# Driver_PT5619_Table_SchDoc.net
KiCad netlist of a schematic drawn in Altium Designer
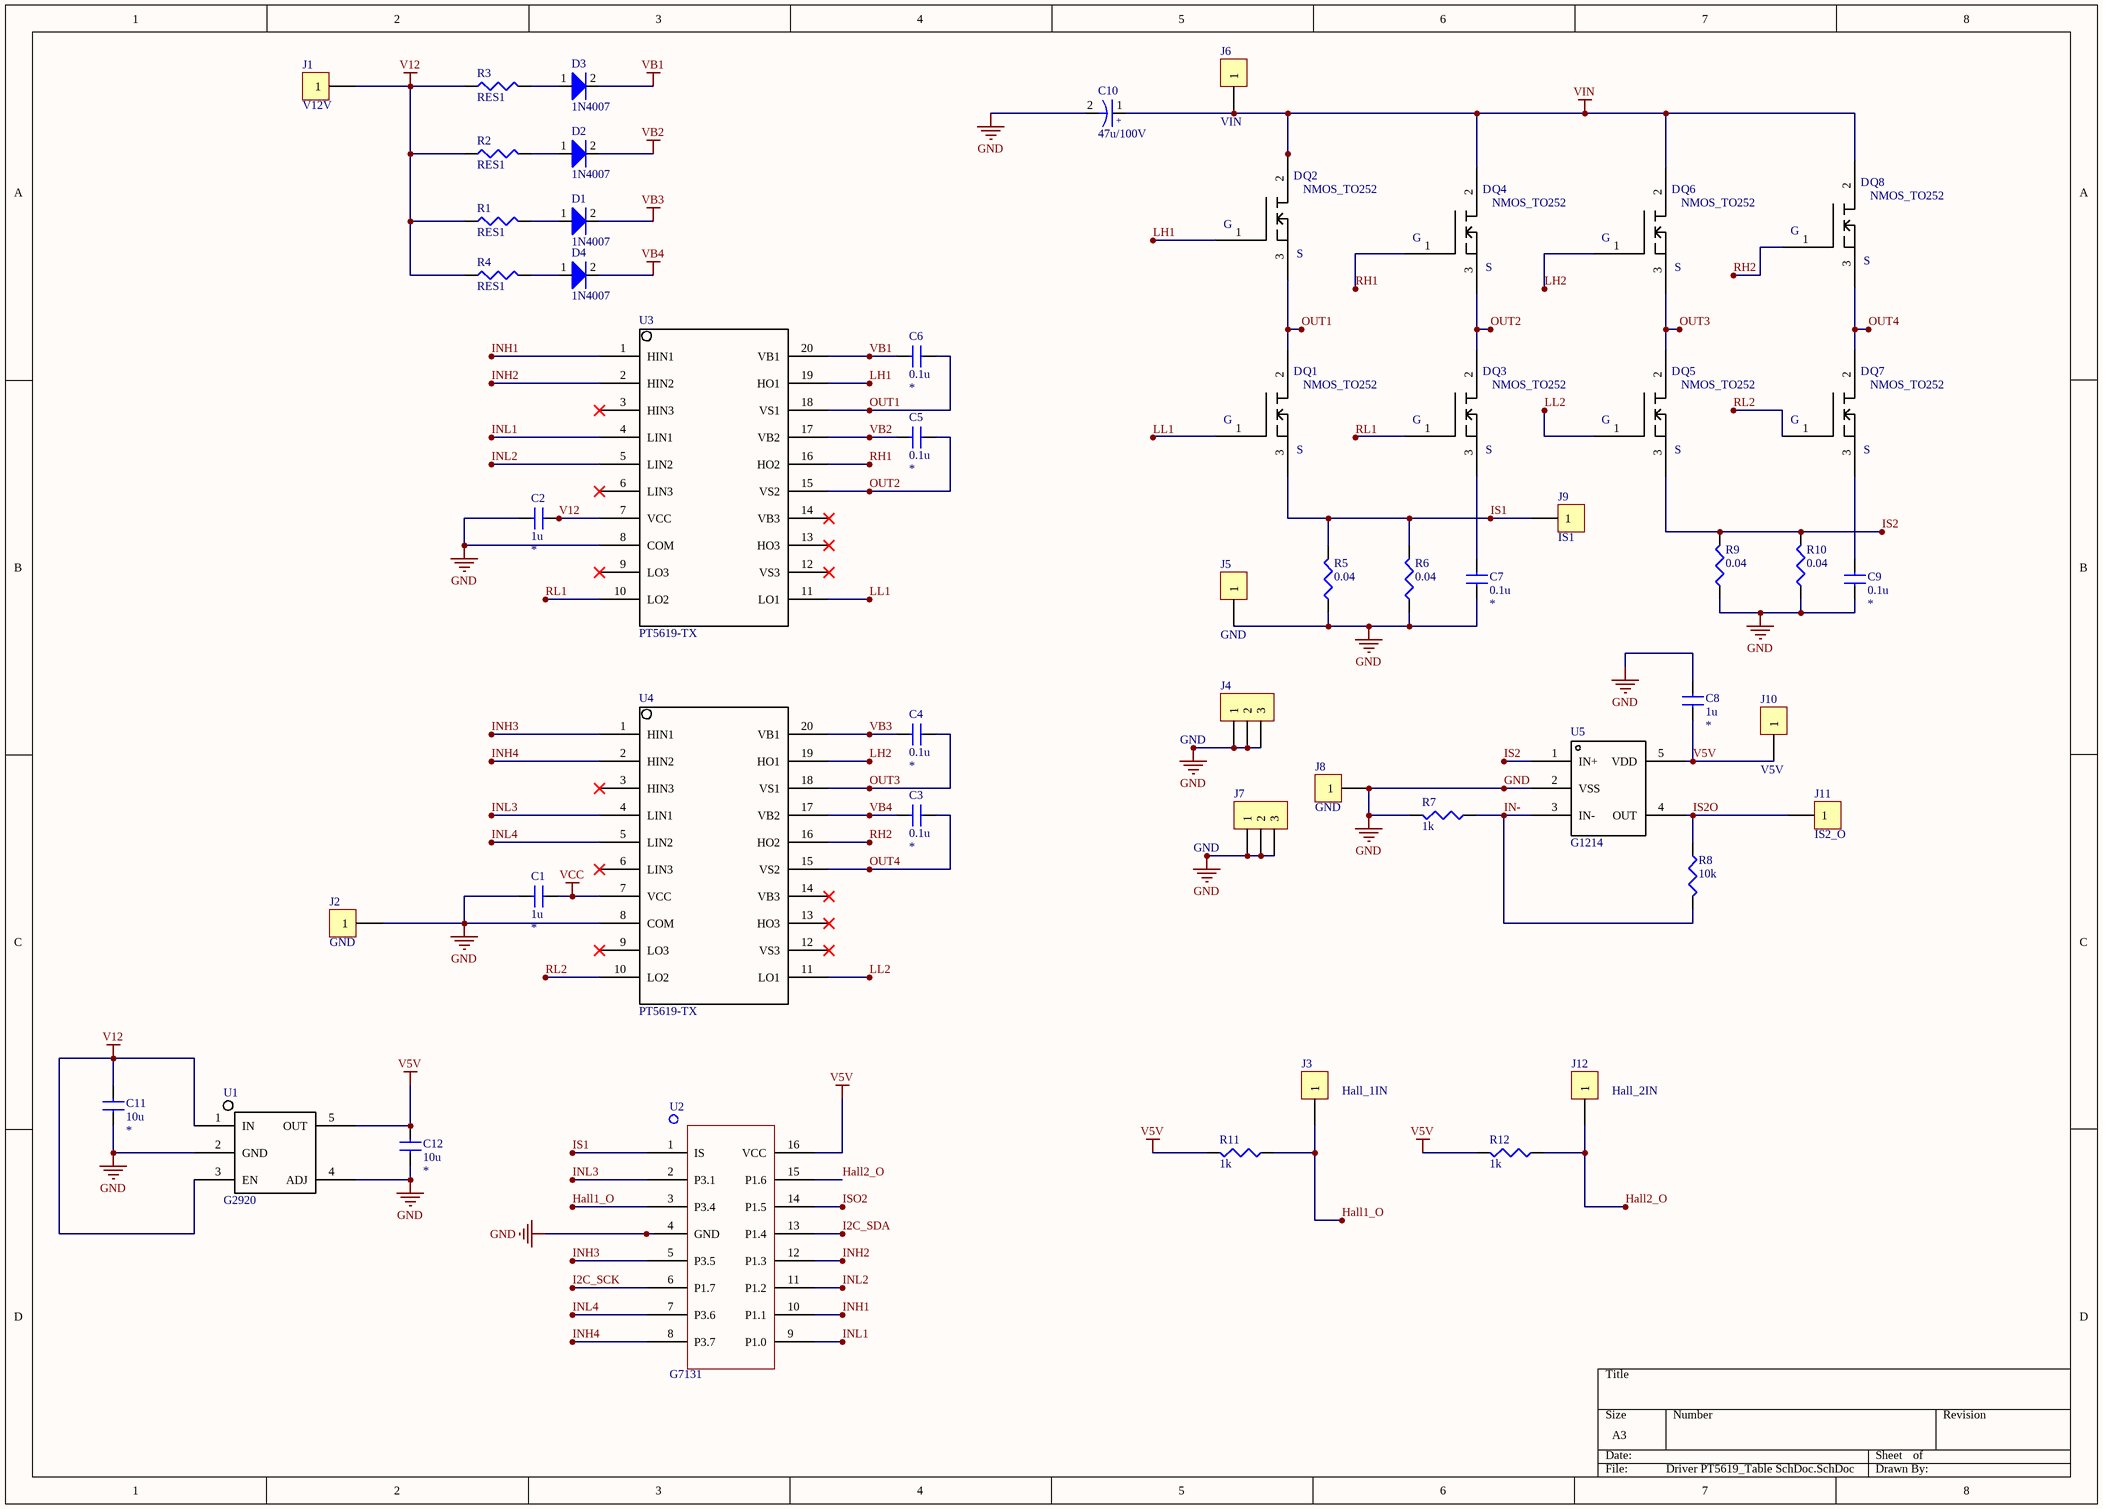
[diagram p0: Driver PT5619_Table SchDoc.SchDoc]

(export (version "E")
  (design (tool "Eeschema 10.0.6"))
  (components
    (comp (ref "C1")
      (value "1u")
      (footprint "0805_C")
      (description "Capacitor")
      (fields (field (name "IC") "*"))
      (libsource (lib "Neil-090810") (part "CAP"))
    )
    (comp (ref "C2")
      (value "1u")
      (footprint "0805_C")
      (description "Capacitor")
      (fields (field (name "IC") "*"))
      (libsource (lib "Neil-090810") (part "CAP"))
    )
    (comp (ref "C3")
      (value "0.1u")
      (footprint "0805_C")
      (description "Capacitor")
      (fields (field (name "IC") "*"))
      (libsource (lib "Neil-090810") (part "CAP"))
    )
    (comp (ref "C4")
      (value "0.1u")
      (footprint "0805_C")
      (description "Capacitor")
      (fields (field (name "IC") "*"))
      (libsource (lib "Neil-090810") (part "CAP"))
    )
    (comp (ref "C5")
      (value "0.1u")
      (footprint "0805_C")
      (description "Capacitor")
      (fields (field (name "IC") "*"))
      (libsource (lib "Neil-090810") (part "CAP"))
    )
    (comp (ref "C6")
      (value "0.1u")
      (footprint "0805_C")
      (description "Capacitor")
      (fields (field (name "IC") "*"))
      (libsource (lib "Neil-090810") (part "CAP"))
    )
    (comp (ref "C7")
      (value "0.1u")
      (footprint "0805_C")
      (description "Capacitor")
      (fields (field (name "IC") "*"))
      (libsource (lib "Neil-090810") (part "CAP"))
    )
    (comp (ref "C8")
      (value "1u")
      (footprint "0805_R")
      (description "Capacitor")
      (fields (field (name "IC") "*"))
      (libsource (lib "Neil-090810") (part "CAP"))
    )
    (comp (ref "C9")
      (value "0.1u")
      (footprint "0805_C")
      (description "Capacitor")
      (fields (field (name "IC") "*"))
      (libsource (lib "Neil-090810") (part "CAP"))
    )
    (comp (ref "C10")
      (value "47u/100V")
      (description "Capacitor")
      (libsource (lib "Neil-090810") (part "CAPACITOR POL"))
    )
    (comp (ref "C11")
      (value "10u")
      (description "Capacitor")
      (fields (field (name "IC") "*"))
      (libsource (lib "Neil-090810") (part "CAP"))
    )
    (comp (ref "C12")
      (value "10u")
      (description "Capacitor")
      (fields (field (name "IC") "*"))
      (libsource (lib "Neil-090810") (part "CAP"))
    )
    (comp (ref "D1")
      (value "1N4007")
      (footprint "DIODE-1206")
      (description "Junction Diode")
      (libsource (lib "Neil-090810") (part "DIODE_D"))
    )
    (comp (ref "D2")
      (value "1N4007")
      (footprint "DIODE-1206")
      (description "Junction Diode")
      (libsource (lib "Neil-090810") (part "DIODE_D"))
    )
    (comp (ref "D3")
      (value "1N4007")
      (footprint "DIODE-1206")
      (description "Junction Diode")
      (libsource (lib "Neil-090810") (part "DIODE_D"))
    )
    (comp (ref "D4")
      (value "1N4007")
      (footprint "DIODE-1206")
      (description "Junction Diode")
      (libsource (lib "Neil-090810") (part "DIODE_D"))
    )
    (comp (ref "J1")
      (value "V12V")
      (footprint "CON1")
      (description "Connector")
      (libsource (lib "") (part "CON1_2"))
    )
    (comp (ref "J2")
      (value "GND")
      (footprint "CON1")
      (description "Connector")
      (libsource (lib "") (part "CON1_2"))
    )
    (comp (ref "J3")
      (value "Hall_1IN")
      (description "Connector")
      (libsource (lib "Neil-090810") (part "CON1"))
    )
    (comp (ref "J4")
      (value "GND")
      (footprint "CON3")
      (description "Connector")
      (libsource (lib "Neil-090810") (part "CON3"))
    )
    (comp (ref "J5")
      (value "GND")
      (footprint "CON1")
      (description "Connector")
      (libsource (lib "Neil-090810") (part "CON1"))
    )
    (comp (ref "J6")
      (value "VIN")
      (footprint "CON1")
      (description "Connector")
      (libsource (lib "Neil-090810") (part "CON1"))
    )
    (comp (ref "J7")
      (value "GND")
      (footprint "CON3")
      (description "Connector")
      (libsource (lib "Neil-090810") (part "CON3"))
    )
    (comp (ref "J8")
      (value "GND")
      (footprint "CON1")
      (description "Connector")
      (libsource (lib "") (part "CON1_2"))
    )
    (comp (ref "J9")
      (value "IS1")
      (footprint "CON1s")
      (description "Connector")
      (libsource (lib "") (part "CON1_1"))
    )
    (comp (ref "J10")
      (value "V5V")
      (footprint "CON1")
      (description "Connector")
      (libsource (lib "Neil-090810") (part "CON1"))
    )
    (comp (ref "J11")
      (value "IS2_O")
      (footprint "CON1s")
      (description "Connector")
      (libsource (lib "") (part "CON1_1"))
    )
    (comp (ref "J12")
      (value "Hall_2IN")
      (description "Connector")
      (libsource (lib "Neil-090810") (part "CON1"))
    )
    (comp (ref "Q1")
      (value "NMOS_TO252")
      (footprint "TO220")
      (libsource (lib "Neil-090810") (part "NMOS_TO252"))
    )
    (comp (ref "Q2")
      (value "NMOS_TO252")
      (footprint "TO220")
      (libsource (lib "Neil-090810") (part "NMOS_TO252"))
    )
    (comp (ref "Q3")
      (value "NMOS_TO252")
      (footprint "TO220")
      (libsource (lib "Neil-090810") (part "NMOS_TO252"))
    )
    (comp (ref "Q4")
      (value "NMOS_TO252")
      (footprint "TO220")
      (libsource (lib "Neil-090810") (part "NMOS_TO252"))
    )
    (comp (ref "Q5")
      (value "NMOS_TO252")
      (footprint "TO220 - duplicate")
      (libsource (lib "Neil-090810") (part "NMOS_TO252"))
    )
    (comp (ref "Q6")
      (value "NMOS_TO252")
      (footprint "TO220")
      (libsource (lib "Neil-090810") (part "NMOS_TO252"))
    )
    (comp (ref "Q7")
      (value "NMOS_TO252")
      (footprint "TO220")
      (libsource (lib "Neil-090810") (part "NMOS_TO252"))
    )
    (comp (ref "Q8")
      (value "NMOS_TO252")
      (footprint "TO220")
      (libsource (lib "Neil-090810") (part "NMOS_TO252"))
    )
    (comp (ref "R1") (value "RES1") (footprint "0805_R") (libsource (lib "Neil-090810") (part "RES1")))
    (comp (ref "R2") (value "RES1") (footprint "0805_R") (libsource (lib "Neil-090810") (part "RES1")))
    (comp (ref "R3") (value "RES1") (footprint "0805_R") (libsource (lib "Neil-090810") (part "RES1")))
    (comp (ref "R4") (value "RES1") (footprint "0805_R") (libsource (lib "Neil-090810") (part "RES1")))
    (comp (ref "R5") (value "0.04") (footprint "2512") (libsource (lib "Neil-090810") (part "RES1")))
    (comp (ref "R6") (value "0.04") (footprint "2512") (libsource (lib "Neil-090810") (part "RES1")))
    (comp (ref "R7") (value "1k") (footprint "0805_R") (libsource (lib "Neil-090810") (part "RES1")))
    (comp (ref "R8") (value "10k") (footprint "0805_R") (libsource (lib "Neil-090810") (part "RES1")))
    (comp (ref "R9") (value "0.04") (footprint "2512") (libsource (lib "Neil-090810") (part "RES1")))
    (comp (ref "R10") (value "0.04") (footprint "2512") (libsource (lib "Neil-090810") (part "RES1")))
    (comp (ref "R11") (value "1k") (libsource (lib "Neil-090810") (part "RES1")))
    (comp (ref "R12") (value "1k") (libsource (lib "Neil-090810") (part "RES1")))
    (comp (ref "U1") (value "G2920") (libsource (lib "Neil-090810") (part "G2920")))
    (comp (ref "U2") (value "G7131") (libsource (lib "Neil-090810") (part "G7131")))
    (comp (ref "U3")
      (value "PT5619-TX")
      (footprint "TSSOP20")
      (libsource (lib "Neil-090810") (part "PT5619-TX"))
    )
    (comp (ref "U4")
      (value "PT5619-TX")
      (footprint "TSSOP20")
      (libsource (lib "Neil-090810") (part "PT5619-TX"))
    )
    (comp (ref "U5")
      (value "G1214")
      (footprint "SOT-23-5-G1211")
      (libsource (lib "Neil-090810") (part "G1214"))
    )
  )
  (nets
    (net (code "1") (name "/Hall1_O") (class "Default")
      (node (ref "J3") (pin "1") (pinfunction "1_1") (pintype "passive"))
      (node (ref "R11") (pin "1") (pinfunction "1_1") (pintype "passive"))
      (node (ref "U2") (pin "3") (pinfunction "P3.4_3") (pintype "passive"))
    )
    (net (code "2") (name "/Hall2_O") (class "Default")
      (node (ref "J12") (pin "1") (pinfunction "1_1") (pintype "passive"))
      (node (ref "R12") (pin "1") (pinfunction "1_1") (pintype "passive"))
      (node (ref "U2") (pin "15") (pinfunction "P1.6_15") (pintype "passive"))
    )
    (net (code "3") (name "/I2C_SCK") (class "Default")
      (node (ref "U2") (pin "6") (pinfunction "P1.7_6") (pintype "passive"))
    )
    (net (code "4") (name "/I2C_SDA") (class "Default")
      (node (ref "U2") (pin "13") (pinfunction "P1.4_13") (pintype "passive"))
    )
    (net (code "5") (name "/IN-") (class "Default")
      (node (ref "R7") (pin "1") (pinfunction "1_1") (pintype "passive"))
      (node (ref "R8") (pin "2") (pinfunction "2_2") (pintype "passive"))
      (node (ref "U5") (pin "3") (pinfunction "IN-_3") (pintype "passive"))
    )
    (net (code "6") (name "/INH1") (class "Default")
      (node (ref "U2") (pin "10") (pinfunction "P1.1_10") (pintype "passive"))
      (node (ref "U3") (pin "1") (pinfunction "HIN1_1") (pintype "passive"))
    )
    (net (code "7") (name "/INH2") (class "Default")
      (node (ref "U2") (pin "12") (pinfunction "P1.3_12") (pintype "passive"))
      (node (ref "U3") (pin "2") (pinfunction "HIN2_2") (pintype "passive"))
    )
    (net (code "8") (name "/INH3") (class "Default")
      (node (ref "U2") (pin "5") (pinfunction "P3.5_5") (pintype "passive"))
      (node (ref "U4") (pin "1") (pinfunction "HIN1_1") (pintype "passive"))
    )
    (net (code "9") (name "/INH4") (class "Default")
      (node (ref "U2") (pin "8") (pinfunction "P3.7_8") (pintype "passive"))
      (node (ref "U4") (pin "2") (pinfunction "HIN2_2") (pintype "passive"))
    )
    (net (code "10") (name "/INL1") (class "Default")
      (node (ref "U2") (pin "9") (pinfunction "P1.0_9") (pintype "passive"))
      (node (ref "U3") (pin "4") (pinfunction "LIN1_4") (pintype "passive"))
    )
    (net (code "11") (name "/INL2") (class "Default")
      (node (ref "U2") (pin "11") (pinfunction "P1.2_11") (pintype "passive"))
      (node (ref "U3") (pin "5") (pinfunction "LIN2_5") (pintype "passive"))
    )
    (net (code "12") (name "/INL3") (class "Default")
      (node (ref "U2") (pin "2") (pinfunction "P3.1_2") (pintype "passive"))
      (node (ref "U4") (pin "4") (pinfunction "LIN1_4") (pintype "passive"))
    )
    (net (code "13") (name "/INL4") (class "Default")
      (node (ref "U2") (pin "7") (pinfunction "P3.6_7") (pintype "passive"))
      (node (ref "U4") (pin "5") (pinfunction "LIN2_5") (pintype "passive"))
    )
    (net (code "14") (name "/IS1") (class "Default")
      (node (ref "J9") (pin "1") (pinfunction "1_1") (pintype "passive"))
      (node (ref "Q1") (pin "3") (pinfunction "S_3") (pintype "passive"))
      (node (ref "R5") (pin "2") (pinfunction "2_2") (pintype "passive"))
      (node (ref "R6") (pin "2") (pinfunction "2_2") (pintype "passive"))
      (node (ref "U2") (pin "1") (pinfunction "IS_1") (pintype "passive"))
    )
    (net (code "15") (name "/IS2") (class "Default")
      (node (ref "Q5") (pin "3") (pinfunction "S_3") (pintype "passive"))
      (node (ref "R10") (pin "2") (pinfunction "2_2") (pintype "passive"))
      (node (ref "R9") (pin "2") (pinfunction "2_2") (pintype "passive"))
      (node (ref "U5") (pin "1") (pinfunction "IN+_1") (pintype "passive"))
    )
    (net (code "16") (name "/IS2O") (class "Default")
      (node (ref "J11") (pin "1") (pinfunction "1_1") (pintype "passive"))
      (node (ref "R8") (pin "1") (pinfunction "1_1") (pintype "passive"))
      (node (ref "U5") (pin "4") (pinfunction "OUT_4") (pintype "passive"))
    )
    (net (code "17") (name "/ISO2") (class "Default")
      (node (ref "U2") (pin "14") (pinfunction "P1.5_14") (pintype "passive"))
    )
    (net (code "18") (name "/LH1") (class "Default")
      (node (ref "Q2") (pin "1") (pinfunction "G_1") (pintype "passive"))
      (node (ref "U3") (pin "19") (pinfunction "HO1_19") (pintype "passive"))
    )
    (net (code "19") (name "/LH2") (class "Default")
      (node (ref "Q6") (pin "1") (pinfunction "G_1") (pintype "passive"))
      (node (ref "U4") (pin "19") (pinfunction "HO1_19") (pintype "passive"))
    )
    (net (code "20") (name "/LL1") (class "Default")
      (node (ref "Q1") (pin "1") (pinfunction "G_1") (pintype "passive"))
      (node (ref "U3") (pin "11") (pinfunction "LO1_11") (pintype "passive"))
    )
    (net (code "21") (name "/LL2") (class "Default")
      (node (ref "Q5") (pin "1") (pinfunction "G_1") (pintype "passive"))
      (node (ref "U4") (pin "11") (pinfunction "LO1_11") (pintype "passive"))
    )
    (net (code "22") (name "/OUT1") (class "Default")
      (node (ref "C6") (pin "2") (pinfunction "2_2") (pintype "passive"))
      (node (ref "Q1") (pin "2") (pinfunction "D_2") (pintype "passive"))
      (node (ref "Q2") (pin "3") (pinfunction "S_3") (pintype "passive"))
      (node (ref "U3") (pin "18") (pinfunction "VS1_18") (pintype "passive"))
    )
    (net (code "23") (name "/OUT2") (class "Default")
      (node (ref "C5") (pin "2") (pinfunction "2_2") (pintype "passive"))
      (node (ref "Q3") (pin "2") (pinfunction "D_2") (pintype "passive"))
      (node (ref "Q4") (pin "3") (pinfunction "S_3") (pintype "passive"))
      (node (ref "U3") (pin "15") (pinfunction "VS2_15") (pintype "passive"))
    )
    (net (code "24") (name "/OUT3") (class "Default")
      (node (ref "C4") (pin "2") (pinfunction "2_2") (pintype "passive"))
      (node (ref "Q5") (pin "2") (pinfunction "D_2") (pintype "passive"))
      (node (ref "Q6") (pin "3") (pinfunction "S_3") (pintype "passive"))
      (node (ref "U4") (pin "18") (pinfunction "VS1_18") (pintype "passive"))
    )
    (net (code "25") (name "/OUT4") (class "Default")
      (node (ref "C3") (pin "2") (pinfunction "2_2") (pintype "passive"))
      (node (ref "Q7") (pin "2") (pinfunction "D_2") (pintype "passive"))
      (node (ref "Q8") (pin "3") (pinfunction "S_3") (pintype "passive"))
      (node (ref "U4") (pin "15") (pinfunction "VS2_15") (pintype "passive"))
    )
    (net (code "26") (name "/RH1") (class "Default")
      (node (ref "Q4") (pin "1") (pinfunction "G_1") (pintype "passive"))
      (node (ref "U3") (pin "16") (pinfunction "HO2_16") (pintype "passive"))
    )
    (net (code "27") (name "/RH2") (class "Default")
      (node (ref "Q8") (pin "1") (pinfunction "G_1") (pintype "passive"))
      (node (ref "U4") (pin "16") (pinfunction "HO2_16") (pintype "passive"))
    )
    (net (code "28") (name "/RL1") (class "Default")
      (node (ref "Q3") (pin "1") (pinfunction "G_1") (pintype "passive"))
      (node (ref "U3") (pin "10") (pinfunction "LO2_10") (pintype "passive"))
    )
    (net (code "29") (name "/RL2") (class "Default")
      (node (ref "Q7") (pin "1") (pinfunction "G_1") (pintype "passive"))
      (node (ref "U4") (pin "10") (pinfunction "LO2_10") (pintype "passive"))
    )
    (net (code "30") (name "GND") (class "Default")
      (node (ref "C1") (pin "2") (pinfunction "2_2") (pintype "passive"))
      (node (ref "C10") (pin "2") (pinfunction "2_2") (pintype "passive"))
      (node (ref "C11") (pin "2") (pinfunction "2_2") (pintype "passive"))
      (node (ref "C12") (pin "2") (pinfunction "2_2") (pintype "passive"))
      (node (ref "C2") (pin "1") (pinfunction "1_1") (pintype "passive"))
      (node (ref "C7") (pin "2") (pinfunction "2_2") (pintype "passive"))
      (node (ref "C8") (pin "2") (pinfunction "2_2") (pintype "passive"))
      (node (ref "C9") (pin "2") (pinfunction "2_2") (pintype "passive"))
      (node (ref "J2") (pin "1") (pinfunction "1_1") (pintype "passive"))
      (node (ref "J4") (pin "1") (pinfunction "1_1") (pintype "passive"))
      (node (ref "J4") (pin "2") (pinfunction "2_2") (pintype "passive"))
      (node (ref "J4") (pin "3") (pinfunction "3_3") (pintype "passive"))
      (node (ref "J5") (pin "1") (pinfunction "1_1") (pintype "passive"))
      (node (ref "J7") (pin "1") (pinfunction "1_1") (pintype "passive"))
      (node (ref "J7") (pin "2") (pinfunction "2_2") (pintype "passive"))
      (node (ref "J7") (pin "3") (pinfunction "3_3") (pintype "passive"))
      (node (ref "J8") (pin "1") (pinfunction "1_1") (pintype "passive"))
      (node (ref "R10") (pin "1") (pinfunction "1_1") (pintype "passive"))
      (node (ref "R5") (pin "1") (pinfunction "1_1") (pintype "passive"))
      (node (ref "R6") (pin "1") (pinfunction "1_1") (pintype "passive"))
      (node (ref "R7") (pin "2") (pinfunction "2_2") (pintype "passive"))
      (node (ref "R9") (pin "1") (pinfunction "1_1") (pintype "passive"))
      (node (ref "U1") (pin "2") (pinfunction "GND_2") (pintype "passive"))
      (node (ref "U1") (pin "4") (pinfunction "ADJ_4") (pintype "passive"))
      (node (ref "U2") (pin "4") (pinfunction "GND_4") (pintype "passive"))
      (node (ref "U3") (pin "8") (pinfunction "COM_8") (pintype "passive"))
      (node (ref "U4") (pin "8") (pinfunction "COM_8") (pintype "passive"))
      (node (ref "U5") (pin "2") (pinfunction "VSS_2") (pintype "passive"))
    )
    (net (code "31") (name "Net-(D1-n1)") (class "Default")
      (node (ref "D1") (pin "1") (pinfunction "n1_1") (pintype "passive"))
      (node (ref "R1") (pin "2") (pinfunction "2_2") (pintype "passive"))
    )
    (net (code "32") (name "Net-(D2-n1)") (class "Default")
      (node (ref "D2") (pin "1") (pinfunction "n1_1") (pintype "passive"))
      (node (ref "R2") (pin "2") (pinfunction "2_2") (pintype "passive"))
    )
    (net (code "33") (name "Net-(D3-n1)") (class "Default")
      (node (ref "D3") (pin "1") (pinfunction "n1_1") (pintype "passive"))
      (node (ref "R3") (pin "2") (pinfunction "2_2") (pintype "passive"))
    )
    (net (code "34") (name "Net-(D4-n1)") (class "Default")
      (node (ref "D4") (pin "1") (pinfunction "n1_1") (pintype "passive"))
      (node (ref "R4") (pin "2") (pinfunction "2_2") (pintype "passive"))
    )
    (net (code "35") (name "Net-(Q3-S)") (class "Default")
      (node (ref "C7") (pin "1") (pinfunction "1_1") (pintype "passive"))
      (node (ref "Q3") (pin "3") (pinfunction "S_3") (pintype "passive"))
    )
    (net (code "36") (name "Net-(Q7-S)") (class "Default")
      (node (ref "C9") (pin "1") (pinfunction "1_1") (pintype "passive"))
      (node (ref "Q7") (pin "3") (pinfunction "S_3") (pintype "passive"))
    )
    (net (code "37") (name "V5V") (class "Default")
      (node (ref "C12") (pin "1") (pinfunction "1_1") (pintype "passive"))
      (node (ref "C8") (pin "1") (pinfunction "1_1") (pintype "passive"))
      (node (ref "J10") (pin "1") (pinfunction "1_1") (pintype "passive"))
      (node (ref "R11") (pin "2") (pinfunction "2_2") (pintype "passive"))
      (node (ref "R12") (pin "2") (pinfunction "2_2") (pintype "passive"))
      (node (ref "U1") (pin "5") (pinfunction "OUT_5") (pintype "passive"))
      (node (ref "U2") (pin "16") (pinfunction "VCC_16") (pintype "passive"))
      (node (ref "U5") (pin "5") (pinfunction "VDD_5") (pintype "passive"))
    )
    (net (code "38") (name "V12") (class "Default")
      (node (ref "C11") (pin "1") (pinfunction "1_1") (pintype "passive"))
      (node (ref "C2") (pin "2") (pinfunction "2_2") (pintype "passive"))
      (node (ref "J1") (pin "1") (pinfunction "1_1") (pintype "passive"))
      (node (ref "R1") (pin "1") (pinfunction "1_1") (pintype "passive"))
      (node (ref "R2") (pin "1") (pinfunction "1_1") (pintype "passive"))
      (node (ref "R3") (pin "1") (pinfunction "1_1") (pintype "passive"))
      (node (ref "R4") (pin "1") (pinfunction "1_1") (pintype "passive"))
      (node (ref "U1") (pin "1") (pinfunction "IN_1") (pintype "passive"))
      (node (ref "U1") (pin "3") (pinfunction "EN_3") (pintype "passive"))
      (node (ref "U3") (pin "7") (pinfunction "VCC_7") (pintype "passive"))
    )
    (net (code "39") (name "VB1") (class "Default")
      (node (ref "C6") (pin "1") (pinfunction "1_1") (pintype "passive"))
      (node (ref "D3") (pin "2") (pinfunction "n2_2") (pintype "passive"))
      (node (ref "U3") (pin "20") (pinfunction "VB1_20") (pintype "passive"))
    )
    (net (code "40") (name "VB2") (class "Default")
      (node (ref "C5") (pin "1") (pinfunction "1_1") (pintype "passive"))
      (node (ref "D2") (pin "2") (pinfunction "n2_2") (pintype "passive"))
      (node (ref "U3") (pin "17") (pinfunction "VB2_17") (pintype "passive"))
    )
    (net (code "41") (name "VB3") (class "Default")
      (node (ref "C4") (pin "1") (pinfunction "1_1") (pintype "passive"))
      (node (ref "D1") (pin "2") (pinfunction "n2_2") (pintype "passive"))
      (node (ref "U4") (pin "20") (pinfunction "VB1_20") (pintype "passive"))
    )
    (net (code "42") (name "VB4") (class "Default")
      (node (ref "C3") (pin "1") (pinfunction "1_1") (pintype "passive"))
      (node (ref "D4") (pin "2") (pinfunction "n2_2") (pintype "passive"))
      (node (ref "U4") (pin "17") (pinfunction "VB2_17") (pintype "passive"))
    )
    (net (code "43") (name "VCC") (class "Default")
      (node (ref "C1") (pin "1") (pinfunction "1_1") (pintype "passive"))
      (node (ref "U4") (pin "7") (pinfunction "VCC_7") (pintype "passive"))
    )
    (net (code "44") (name "VIN") (class "Default")
      (node (ref "C10") (pin "1") (pinfunction "1_1") (pintype "passive"))
      (node (ref "J6") (pin "1") (pinfunction "1_1") (pintype "passive"))
      (node (ref "Q2") (pin "2") (pinfunction "D_2") (pintype "passive"))
      (node (ref "Q4") (pin "2") (pinfunction "D_2") (pintype "passive"))
      (node (ref "Q6") (pin "2") (pinfunction "D_2") (pintype "passive"))
      (node (ref "Q8") (pin "2") (pinfunction "D_2") (pintype "passive"))
    )
    (net (code "45") (name "unconnected-(U3-HIN3-Pad3)") (class "Default")
      (node (ref "U3") (pin "3") (pinfunction "HIN3_3") (pintype "passive+no_connect"))
    )
    (net (code "46") (name "unconnected-(U3-HO3-Pad13)") (class "Default")
      (node (ref "U3") (pin "13") (pinfunction "HO3_13") (pintype "passive+no_connect"))
    )
    (net (code "47") (name "unconnected-(U3-LIN3-Pad6)") (class "Default")
      (node (ref "U3") (pin "6") (pinfunction "LIN3_6") (pintype "passive+no_connect"))
    )
    (net (code "48") (name "unconnected-(U3-LO3-Pad9)") (class "Default")
      (node (ref "U3") (pin "9") (pinfunction "LO3_9") (pintype "passive+no_connect"))
    )
    (net (code "49") (name "unconnected-(U3-VB3-Pad14)") (class "Default")
      (node (ref "U3") (pin "14") (pinfunction "VB3_14") (pintype "passive+no_connect"))
    )
    (net (code "50") (name "unconnected-(U3-VS3-Pad12)") (class "Default")
      (node (ref "U3") (pin "12") (pinfunction "VS3_12") (pintype "passive+no_connect"))
    )
    (net (code "51") (name "unconnected-(U4-HIN3-Pad3)") (class "Default")
      (node (ref "U4") (pin "3") (pinfunction "HIN3_3") (pintype "passive+no_connect"))
    )
    (net (code "52") (name "unconnected-(U4-HO3-Pad13)") (class "Default")
      (node (ref "U4") (pin "13") (pinfunction "HO3_13") (pintype "passive+no_connect"))
    )
    (net (code "53") (name "unconnected-(U4-LIN3-Pad6)") (class "Default")
      (node (ref "U4") (pin "6") (pinfunction "LIN3_6") (pintype "passive+no_connect"))
    )
    (net (code "54") (name "unconnected-(U4-LO3-Pad9)") (class "Default")
      (node (ref "U4") (pin "9") (pinfunction "LO3_9") (pintype "passive+no_connect"))
    )
    (net (code "55") (name "unconnected-(U4-VB3-Pad14)") (class "Default")
      (node (ref "U4") (pin "14") (pinfunction "VB3_14") (pintype "passive+no_connect"))
    )
    (net (code "56") (name "unconnected-(U4-VS3-Pad12)") (class "Default")
      (node (ref "U4") (pin "12") (pinfunction "VS3_12") (pintype "passive+no_connect"))
    )
  )
)
